# 1A20J7_1A21J7_A.net
KiCad netlist of a schematic drawn in Altium Designer
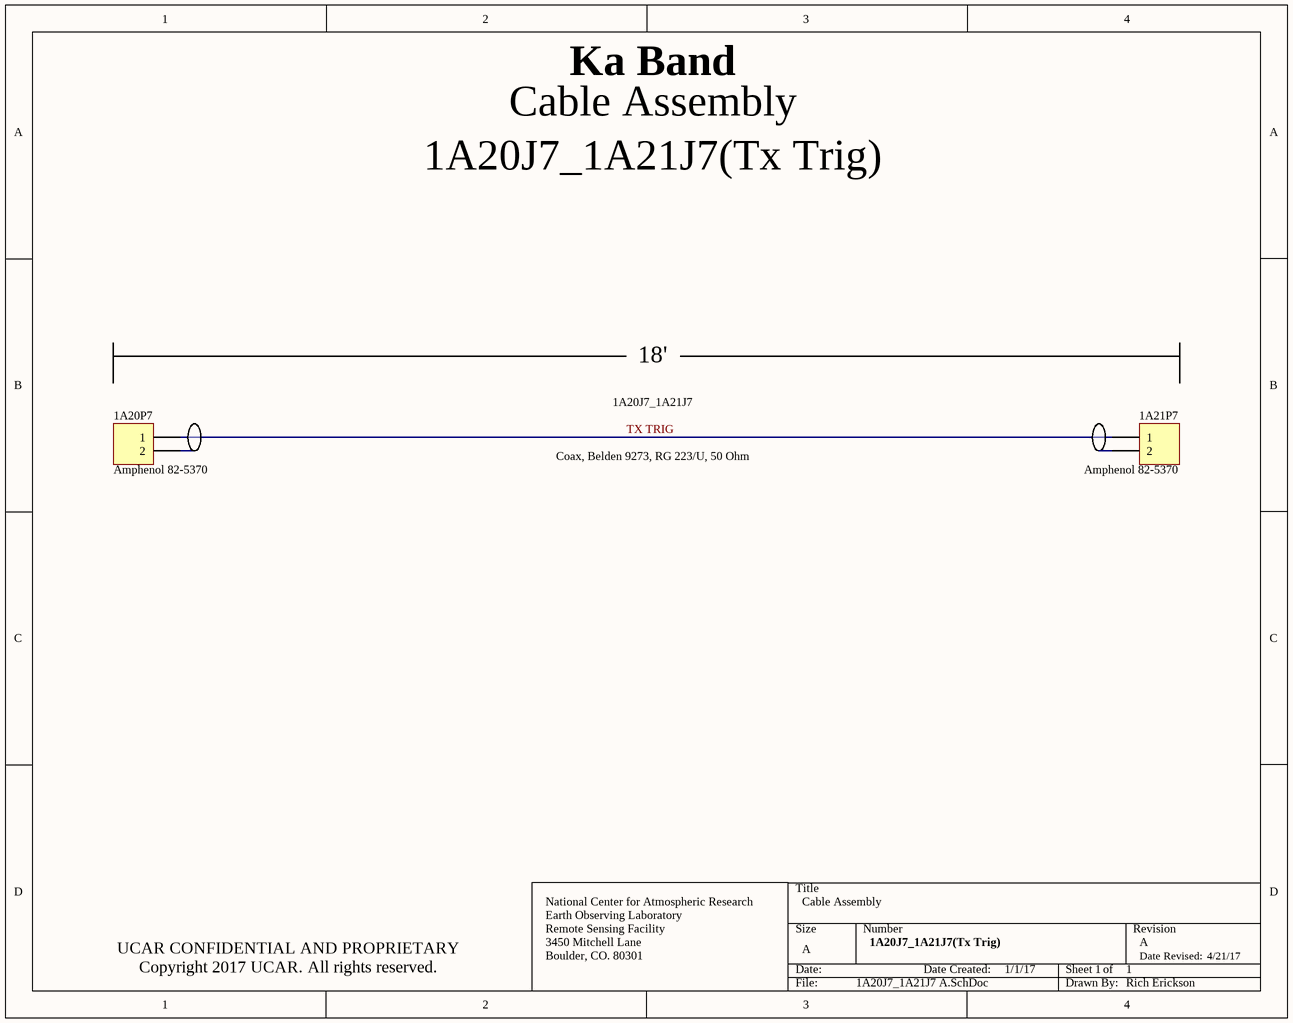
[diagram p0: 1A20J7_1A21J7 A.SchDoc]

(export (version "E")
  (design (tool "Eeschema 10.0.6"))
  (components
    (comp (ref "1A20P7")
      (value "Amphenol 82-5370")
      (footprint "HDR1X2")
      (description "Header, 2-Pin")
      (fields (field (name "PUBLISHER") "Altium Limited"))
      (libsource (lib "") (part "Header 2_1"))
    )
    (comp (ref "1A21P7")
      (value "Amphenol 82-5370")
      (footprint "HDR1X2")
      (description "Header, 2-Pin")
      (fields (field (name "PUBLISHER") "Altium Limited"))
      (libsource (lib "Miscellaneous Connectors") (part "Header 2"))
    )
  )
  (nets
    (net (code "1") (name "/TX TRIG") (class "Default")
      (node (ref "1A20P7") (pin "1") (pinfunction "1_1") (pintype "passive"))
      (node (ref "1A21P7") (pin "1") (pinfunction "1_1") (pintype "passive"))
    )
    (net (code "2") (name "unconnected-(1A20P7-Pad2)") (class "Default")
      (node (ref "1A20P7") (pin "2") (pinfunction "2_2") (pintype "passive"))
    )
    (net (code "3") (name "unconnected-(1A21P7-Pad2)") (class "Default")
      (node (ref "1A21P7") (pin "2") (pinfunction "2_2") (pintype "passive"))
    )
  )
)
